# Logic_SchematicV4-NEW.net
KiCad netlist of a schematic drawn in EAGLE
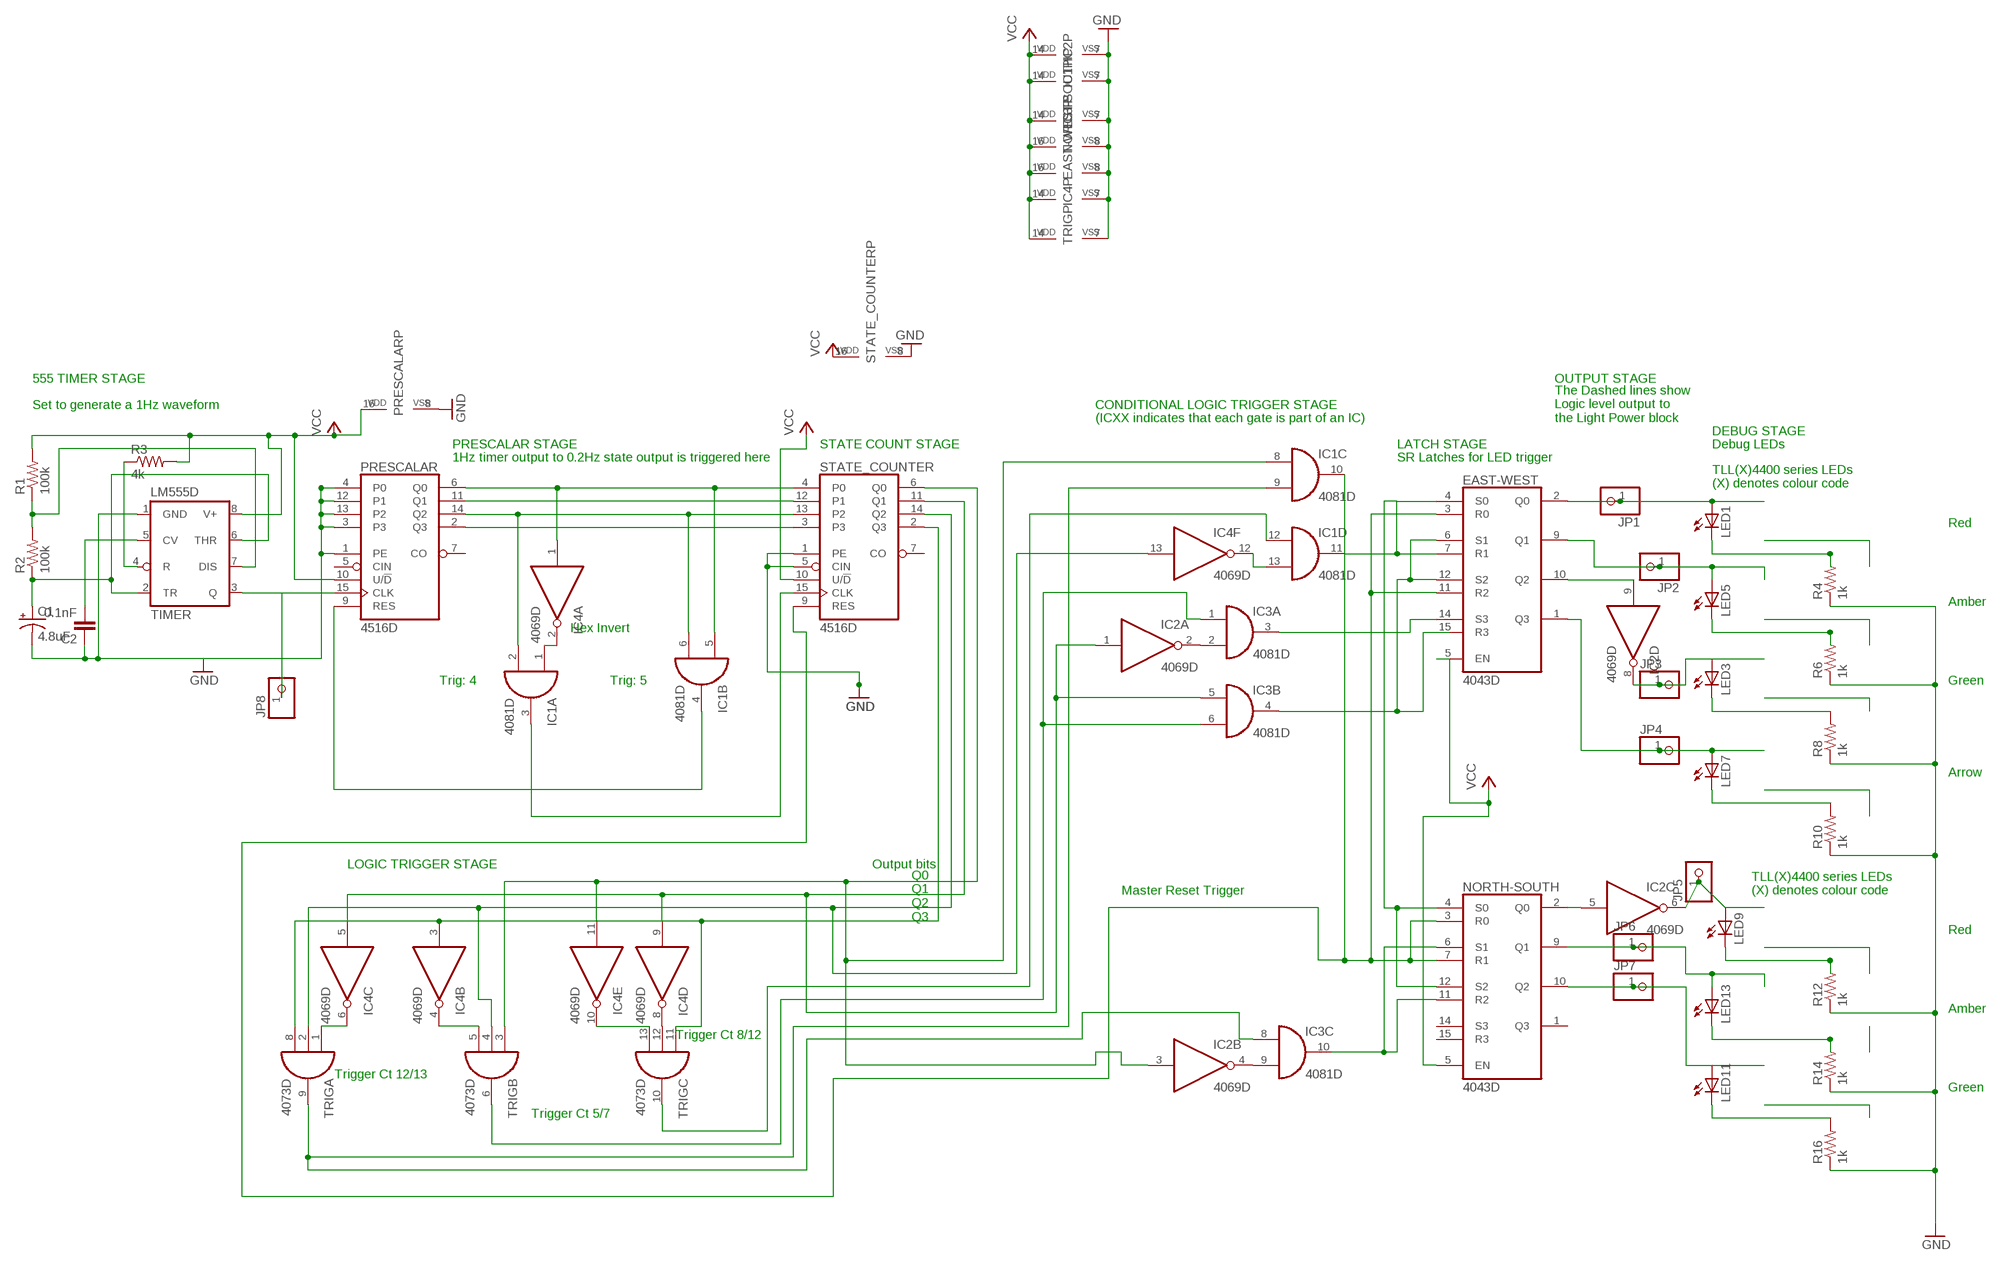
[diagram p0: schematic, sheet 1]

(export (version "E")
  (design (tool "Eeschema 10.0.6"))
  (components
    (comp (ref "C1")
      (value "4.8uF")
      (footprint "eagle-import:E5-8,5")
      (libsource (lib "eagle-import") (part "CPOL-USE5-8.5"))
    )
    (comp (ref "C2")
      (value "0.1nF")
      (footprint "eagle-import:C0805")
      (libsource (lib "eagle-import") (part "C-EUC0805"))
    )
    (comp (ref "EAST-WEST")
      (value "4043D")
      (footprint "eagle-import:SO16")
      (libsource (lib "eagle-import") (part "4043D"))
    )
    (comp (ref "IC1")
      (value "4081D")
      (footprint "eagle-import:SO14")
      (libsource (lib "eagle-import") (part "4081D"))
    )
    (comp (ref "IC2")
      (value "4069D")
      (footprint "eagle-import:SO14")
      (libsource (lib "eagle-import") (part "4069D"))
    )
    (comp (ref "IC3")
      (value "4081D")
      (footprint "eagle-import:SO14")
      (libsource (lib "eagle-import") (part "4081D"))
    )
    (comp (ref "IC4")
      (value "4069D")
      (footprint "eagle-import:SO14")
      (libsource (lib "eagle-import") (part "4069D"))
    )
    (comp (ref "JP1")
      (value "PINHD-1X1")
      (footprint "eagle-import:1X01")
      (libsource (lib "eagle-import") (part "PINHD-1X1"))
    )
    (comp (ref "JP2")
      (value "PINHD-1X1")
      (footprint "eagle-import:1X01")
      (libsource (lib "eagle-import") (part "PINHD-1X1"))
    )
    (comp (ref "JP3")
      (value "PINHD-1X1")
      (footprint "eagle-import:1X01")
      (libsource (lib "eagle-import") (part "PINHD-1X1"))
    )
    (comp (ref "JP4")
      (value "PINHD-1X1")
      (footprint "eagle-import:1X01")
      (libsource (lib "eagle-import") (part "PINHD-1X1"))
    )
    (comp (ref "JP5")
      (value "PINHD-1X1")
      (footprint "eagle-import:1X01")
      (libsource (lib "eagle-import") (part "PINHD-1X1"))
    )
    (comp (ref "JP6")
      (value "PINHD-1X1")
      (footprint "eagle-import:1X01")
      (libsource (lib "eagle-import") (part "PINHD-1X1"))
    )
    (comp (ref "JP7")
      (value "PINHD-1X1")
      (footprint "eagle-import:1X01")
      (libsource (lib "eagle-import") (part "PINHD-1X1"))
    )
    (comp (ref "JP8")
      (value "PINHD-1X1")
      (footprint "eagle-import:1X01")
      (libsource (lib "eagle-import") (part "PINHD-1X1"))
    )
    (comp (ref "LED1")
      (value "LEDCHIP-LED0805")
      (footprint "eagle-import:CHIP-LED0805")
      (libsource (lib "eagle-import") (part "LEDCHIP-LED0805"))
    )
    (comp (ref "LED3")
      (value "LEDCHIP-LED0805")
      (footprint "eagle-import:CHIP-LED0805")
      (libsource (lib "eagle-import") (part "LEDCHIP-LED0805"))
    )
    (comp (ref "LED5")
      (value "LEDCHIP-LED0805")
      (footprint "eagle-import:CHIP-LED0805")
      (libsource (lib "eagle-import") (part "LEDCHIP-LED0805"))
    )
    (comp (ref "LED7")
      (value "LEDCHIP-LED0805")
      (footprint "eagle-import:CHIP-LED0805")
      (libsource (lib "eagle-import") (part "LEDCHIP-LED0805"))
    )
    (comp (ref "LED9")
      (value "LEDCHIP-LED0805")
      (footprint "eagle-import:CHIP-LED0805")
      (libsource (lib "eagle-import") (part "LEDCHIP-LED0805"))
    )
    (comp (ref "LED11")
      (value "LEDCHIP-LED0805")
      (footprint "eagle-import:CHIP-LED0805")
      (libsource (lib "eagle-import") (part "LEDCHIP-LED0805"))
    )
    (comp (ref "LED13")
      (value "LEDCHIP-LED0805")
      (footprint "eagle-import:CHIP-LED0805")
      (libsource (lib "eagle-import") (part "LEDCHIP-LED0805"))
    )
    (comp (ref "NORTH-SOUTH")
      (value "4043D")
      (footprint "eagle-import:SO16")
      (libsource (lib "eagle-import") (part "4043D"))
    )
    (comp (ref "PRESCALAR")
      (value "4516D")
      (footprint "eagle-import:SO16")
      (libsource (lib "eagle-import") (part "4516D"))
    )
    (comp (ref "R1")
      (value "100k")
      (footprint "eagle-import:M0805")
      (libsource (lib "eagle-import") (part "R-US_M0805"))
    )
    (comp (ref "R2")
      (value "100k")
      (footprint "eagle-import:M0805")
      (libsource (lib "eagle-import") (part "R-US_M0805"))
    )
    (comp (ref "R3")
      (value "4k")
      (footprint "eagle-import:M0805")
      (libsource (lib "eagle-import") (part "R-US_M0805"))
    )
    (comp (ref "R4")
      (value "1k")
      (footprint "eagle-import:M0805")
      (libsource (lib "eagle-import") (part "R-US_M0805"))
    )
    (comp (ref "R6")
      (value "1k")
      (footprint "eagle-import:M0805")
      (libsource (lib "eagle-import") (part "R-US_M0805"))
    )
    (comp (ref "R8")
      (value "1k")
      (footprint "eagle-import:M0805")
      (libsource (lib "eagle-import") (part "R-US_M0805"))
    )
    (comp (ref "R10")
      (value "1k")
      (footprint "eagle-import:M0805")
      (libsource (lib "eagle-import") (part "R-US_M0805"))
    )
    (comp (ref "R12")
      (value "1k")
      (footprint "eagle-import:M0805")
      (libsource (lib "eagle-import") (part "R-US_M0805"))
    )
    (comp (ref "R14")
      (value "1k")
      (footprint "eagle-import:M0805")
      (libsource (lib "eagle-import") (part "R-US_M0805"))
    )
    (comp (ref "R16")
      (value "1k")
      (footprint "eagle-import:M0805")
      (libsource (lib "eagle-import") (part "R-US_M0805"))
    )
    (comp (ref "STATE_COUNTER")
      (value "4516D")
      (footprint "eagle-import:SO16")
      (libsource (lib "eagle-import") (part "4516D"))
    )
    (comp (ref "TIMER")
      (value "LM555D")
      (footprint "eagle-import:SO08")
      (libsource (lib "eagle-import") (part "555DLM"))
    )
    (comp (ref "TRIG")
      (value "4073D")
      (footprint "eagle-import:SO14")
      (libsource (lib "eagle-import") (part "4073D"))
    )
  )
  (nets
    (net (code "1") (name "GND") (class "Default")
      (node (ref "C1") (pin "-") (pinfunction "-_-") (pintype "passive"))
      (node (ref "C2") (pin "1") (pinfunction "1_1") (pintype "passive"))
      (node (ref "EAST-WEST") (pin "8") (pinfunction "VSS_8") (pintype "power_in"))
      (node (ref "IC1") (pin "7") (pinfunction "VSS_7") (pintype "power_in"))
      (node (ref "IC2") (pin "7") (pinfunction "VSS_7") (pintype "power_in"))
      (node (ref "IC3") (pin "7") (pinfunction "VSS_7") (pintype "power_in"))
      (node (ref "IC4") (pin "7") (pinfunction "VSS_7") (pintype "power_in"))
      (node (ref "NORTH-SOUTH") (pin "8") (pinfunction "VSS_8") (pintype "power_in"))
      (node (ref "PRESCALAR") (pin "1") (pinfunction "PE_1") (pintype "input"))
      (node (ref "PRESCALAR") (pin "12") (pinfunction "P1_12") (pintype "input"))
      (node (ref "PRESCALAR") (pin "13") (pinfunction "P2_13") (pintype "input"))
      (node (ref "PRESCALAR") (pin "3") (pinfunction "P3_3") (pintype "input"))
      (node (ref "PRESCALAR") (pin "4") (pinfunction "P0_4") (pintype "input"))
      (node (ref "PRESCALAR") (pin "8") (pinfunction "VSS_8") (pintype "power_in"))
      (node (ref "R10") (pin "1") (pinfunction "1_1") (pintype "passive"))
      (node (ref "R12") (pin "1") (pinfunction "1_1") (pintype "passive"))
      (node (ref "R14") (pin "1") (pinfunction "1_1") (pintype "passive"))
      (node (ref "R16") (pin "1") (pinfunction "1_1") (pintype "passive"))
      (node (ref "R4") (pin "1") (pinfunction "1_1") (pintype "passive"))
      (node (ref "R6") (pin "1") (pinfunction "1_1") (pintype "passive"))
      (node (ref "R8") (pin "1") (pinfunction "1_1") (pintype "passive"))
      (node (ref "STATE_COUNTER") (pin "1") (pinfunction "PE_1") (pintype "input"))
      (node (ref "STATE_COUNTER") (pin "5") (pinfunction "CIN_5") (pintype "input"))
      (node (ref "STATE_COUNTER") (pin "8") (pinfunction "VSS_8") (pintype "power_in"))
      (node (ref "TIMER") (pin "1") (pinfunction "GND_1") (pintype "power_in"))
      (node (ref "TRIG") (pin "7") (pinfunction "VSS_7") (pintype "power_in"))
    )
    (net (code "2") (name "Net-(EAST-WESTA-Q0)") (class "Default")
      (node (ref "EAST-WEST") (pin "2") (pinfunction "Q0_2") (pintype "output"))
      (node (ref "JP1") (pin "1") (pinfunction "1_1") (pintype "passive"))
      (node (ref "LED1") (pin "A") (pinfunction "A_A") (pintype "passive"))
    )
    (net (code "3") (name "Net-(EAST-WESTA-Q1)") (class "Default")
      (node (ref "EAST-WEST") (pin "9") (pinfunction "Q1_9") (pintype "output"))
      (node (ref "JP2") (pin "1") (pinfunction "1_1") (pintype "passive"))
      (node (ref "LED5") (pin "A") (pinfunction "A_A") (pintype "passive"))
    )
    (net (code "4") (name "Net-(EAST-WESTA-Q2)") (class "Default")
      (node (ref "EAST-WEST") (pin "10") (pinfunction "Q2_10") (pintype "output"))
      (node (ref "IC2") (pin "9") (pinfunction "I_9") (pintype "input"))
    )
    (net (code "5") (name "Net-(EAST-WESTA-Q3)") (class "Default")
      (node (ref "EAST-WEST") (pin "1") (pinfunction "Q3_1") (pintype "output"))
      (node (ref "JP4") (pin "1") (pinfunction "1_1") (pintype "passive"))
      (node (ref "LED7") (pin "A") (pinfunction "A_A") (pintype "passive"))
    )
    (net (code "6") (name "Net-(EAST-WESTA-R0)") (class "Default")
      (node (ref "EAST-WEST") (pin "11") (pinfunction "R2_11") (pintype "input"))
      (node (ref "EAST-WEST") (pin "3") (pinfunction "R0_3") (pintype "input"))
      (node (ref "IC1") (pin "10") (pinfunction "O_10") (pintype "output"))
      (node (ref "NORTH-SOUTH") (pin "3") (pinfunction "R0_3") (pintype "input"))
      (node (ref "NORTH-SOUTH") (pin "7") (pinfunction "R1_7") (pintype "input"))
      (node (ref "STATE_COUNTER") (pin "9") (pinfunction "RES_9") (pintype "input"))
    )
    (net (code "7") (name "Net-(EAST-WESTA-R1)") (class "Default")
      (node (ref "EAST-WEST") (pin "4") (pinfunction "S0_4") (pintype "input"))
      (node (ref "EAST-WEST") (pin "7") (pinfunction "R1_7") (pintype "input"))
      (node (ref "IC1") (pin "11") (pinfunction "O_11") (pintype "output"))
      (node (ref "NORTH-SOUTH") (pin "12") (pinfunction "S2_12") (pintype "input"))
      (node (ref "NORTH-SOUTH") (pin "4") (pinfunction "S0_4") (pintype "input"))
    )
    (net (code "8") (name "Net-(EAST-WESTA-S1)") (class "Default")
      (node (ref "EAST-WEST") (pin "12") (pinfunction "S2_12") (pintype "input"))
      (node (ref "EAST-WEST") (pin "6") (pinfunction "S1_6") (pintype "input"))
      (node (ref "IC3") (pin "4") (pinfunction "O_4") (pintype "output"))
    )
    (net (code "9") (name "Net-(EAST-WESTA-S3)") (class "Default")
      (node (ref "EAST-WEST") (pin "14") (pinfunction "S3_14") (pintype "input"))
      (node (ref "IC3") (pin "3") (pinfunction "O_3") (pintype "output"))
    )
    (net (code "10") (name "Net-(IC1A-I0)") (class "Default")
      (node (ref "IC1") (pin "1") (pinfunction "I0_1") (pintype "input"))
      (node (ref "IC4") (pin "2") (pinfunction "O_2") (pintype "output"))
    )
    (net (code "11") (name "Net-(IC1A-I1)") (class "Default")
      (node (ref "IC1") (pin "2") (pinfunction "I1_2") (pintype "input"))
      (node (ref "IC1") (pin "6") (pinfunction "I1_6") (pintype "input"))
      (node (ref "PRESCALAR") (pin "14") (pinfunction "Q2_14") (pintype "output"))
      (node (ref "STATE_COUNTER") (pin "13") (pinfunction "P2_13") (pintype "input"))
    )
    (net (code "12") (name "Net-(IC1A-O)") (class "Default")
      (node (ref "IC1") (pin "3") (pinfunction "O_3") (pintype "output"))
      (node (ref "STATE_COUNTER") (pin "15") (pinfunction "CLK_15") (pintype "input"))
    )
    (net (code "13") (name "Net-(IC1B-I0)") (class "Default")
      (node (ref "IC1") (pin "5") (pinfunction "I0_5") (pintype "input"))
      (node (ref "IC4") (pin "1") (pinfunction "I_1") (pintype "input"))
      (node (ref "PRESCALAR") (pin "6") (pinfunction "Q0_6") (pintype "output"))
      (node (ref "STATE_COUNTER") (pin "4") (pinfunction "P0_4") (pintype "input"))
    )
    (net (code "14") (name "Net-(IC1B-O)") (class "Default")
      (node (ref "IC1") (pin "4") (pinfunction "O_4") (pintype "output"))
      (node (ref "PRESCALAR") (pin "9") (pinfunction "RES_9") (pintype "input"))
    )
    (net (code "15") (name "Net-(IC1C-I0)") (class "Default")
      (node (ref "IC1") (pin "8") (pinfunction "I0_8") (pintype "input"))
      (node (ref "IC2") (pin "3") (pinfunction "I_3") (pintype "input"))
      (node (ref "IC4") (pin "11") (pinfunction "I_11") (pintype "input"))
      (node (ref "STATE_COUNTER") (pin "6") (pinfunction "Q0_6") (pintype "output"))
      (node (ref "TRIG") (pin "3") (pinfunction "I0_3") (pintype "input"))
    )
    (net (code "16") (name "Net-(IC1C-I1)") (class "Default")
      (node (ref "IC1") (pin "9") (pinfunction "I1_9") (pintype "input"))
      (node (ref "IC3") (pin "8") (pinfunction "I0_8") (pintype "input"))
      (node (ref "TRIG") (pin "9") (pinfunction "O_9") (pintype "output"))
    )
    (net (code "17") (name "Net-(IC1D-I0)") (class "Default")
      (node (ref "IC1") (pin "12") (pinfunction "I0_12") (pintype "input"))
      (node (ref "TRIG") (pin "10") (pinfunction "O_10") (pintype "output"))
    )
    (net (code "18") (name "Net-(IC1D-I1)") (class "Default")
      (node (ref "IC1") (pin "13") (pinfunction "I1_13") (pintype "input"))
      (node (ref "IC4") (pin "12") (pinfunction "O_12") (pintype "output"))
    )
    (net (code "19") (name "Net-(IC2A-I)") (class "Default")
      (node (ref "IC2") (pin "1") (pinfunction "I_1") (pintype "input"))
      (node (ref "IC3") (pin "5") (pinfunction "I0_5") (pintype "input"))
      (node (ref "IC4") (pin "5") (pinfunction "I_5") (pintype "input"))
      (node (ref "IC4") (pin "9") (pinfunction "I_9") (pintype "input"))
      (node (ref "STATE_COUNTER") (pin "11") (pinfunction "Q1_11") (pintype "output"))
    )
    (net (code "20") (name "Net-(IC2A-O)") (class "Default")
      (node (ref "IC2") (pin "2") (pinfunction "O_2") (pintype "output"))
      (node (ref "IC3") (pin "2") (pinfunction "I1_2") (pintype "input"))
    )
    (net (code "21") (name "Net-(IC2B-O)") (class "Default")
      (node (ref "IC2") (pin "4") (pinfunction "O_4") (pintype "output"))
      (node (ref "IC3") (pin "9") (pinfunction "I1_9") (pintype "input"))
    )
    (net (code "22") (name "Net-(IC2C-I)") (class "Default")
      (node (ref "IC2") (pin "5") (pinfunction "I_5") (pintype "input"))
      (node (ref "NORTH-SOUTH") (pin "2") (pinfunction "Q0_2") (pintype "output"))
    )
    (net (code "23") (name "Net-(IC2C-O)") (class "Default")
      (node (ref "IC2") (pin "6") (pinfunction "O_6") (pintype "output"))
      (node (ref "JP5") (pin "1") (pinfunction "1_1") (pintype "passive"))
      (node (ref "LED9") (pin "A") (pinfunction "A_A") (pintype "passive"))
    )
    (net (code "24") (name "Net-(IC2D-O)") (class "Default")
      (node (ref "IC2") (pin "8") (pinfunction "O_8") (pintype "output"))
      (node (ref "JP3") (pin "1") (pinfunction "1_1") (pintype "passive"))
      (node (ref "LED3") (pin "A") (pinfunction "A_A") (pintype "passive"))
    )
    (net (code "25") (name "Net-(IC3A-I0)") (class "Default")
      (node (ref "IC3") (pin "1") (pinfunction "I0_1") (pintype "input"))
      (node (ref "IC3") (pin "6") (pinfunction "I1_6") (pintype "input"))
      (node (ref "TRIG") (pin "6") (pinfunction "O_6") (pintype "output"))
    )
    (net (code "26") (name "Net-(IC3C-O)") (class "Default")
      (node (ref "IC3") (pin "10") (pinfunction "O_10") (pintype "output"))
      (node (ref "NORTH-SOUTH") (pin "11") (pinfunction "R2_11") (pintype "input"))
      (node (ref "NORTH-SOUTH") (pin "6") (pinfunction "S1_6") (pintype "input"))
    )
    (net (code "27") (name "Net-(IC4B-I)") (class "Default")
      (node (ref "IC4") (pin "3") (pinfunction "I_3") (pintype "input"))
      (node (ref "STATE_COUNTER") (pin "2") (pinfunction "Q3_2") (pintype "output"))
      (node (ref "TRIG") (pin "11") (pinfunction "I0_11") (pintype "input"))
      (node (ref "TRIG") (pin "8") (pinfunction "I2_8") (pintype "input"))
    )
    (net (code "28") (name "Net-(IC4B-O)") (class "Default")
      (node (ref "IC4") (pin "4") (pinfunction "O_4") (pintype "output"))
      (node (ref "TRIG") (pin "5") (pinfunction "I2_5") (pintype "input"))
    )
    (net (code "29") (name "Net-(IC4C-O)") (class "Default")
      (node (ref "IC4") (pin "6") (pinfunction "O_6") (pintype "output"))
      (node (ref "TRIG") (pin "1") (pinfunction "I0_1") (pintype "input"))
    )
    (net (code "30") (name "Net-(IC4D-O)") (class "Default")
      (node (ref "IC4") (pin "8") (pinfunction "O_8") (pintype "output"))
      (node (ref "TRIG") (pin "12") (pinfunction "I1_12") (pintype "input"))
    )
    (net (code "31") (name "Net-(IC4E-O)") (class "Default")
      (node (ref "IC4") (pin "10") (pinfunction "O_10") (pintype "output"))
      (node (ref "TRIG") (pin "13") (pinfunction "I2_13") (pintype "input"))
    )
    (net (code "32") (name "Net-(IC4F-I)") (class "Default")
      (node (ref "IC4") (pin "13") (pinfunction "I_13") (pintype "input"))
      (node (ref "STATE_COUNTER") (pin "14") (pinfunction "Q2_14") (pintype "output"))
      (node (ref "TRIG") (pin "2") (pinfunction "I1_2") (pintype "input"))
      (node (ref "TRIG") (pin "4") (pinfunction "I1_4") (pintype "input"))
    )
    (net (code "33") (name "Net-(LED1-PadC)") (class "Default")
      (node (ref "LED1") (pin "C") (pinfunction "C_C") (pintype "passive"))
      (node (ref "R4") (pin "2") (pinfunction "2_2") (pintype "passive"))
    )
    (net (code "34") (name "Net-(LED3-PadC)") (class "Default")
      (node (ref "LED3") (pin "C") (pinfunction "C_C") (pintype "passive"))
      (node (ref "R8") (pin "2") (pinfunction "2_2") (pintype "passive"))
    )
    (net (code "35") (name "Net-(LED5-PadC)") (class "Default")
      (node (ref "LED5") (pin "C") (pinfunction "C_C") (pintype "passive"))
      (node (ref "R6") (pin "2") (pinfunction "2_2") (pintype "passive"))
    )
    (net (code "36") (name "Net-(LED7-PadC)") (class "Default")
      (node (ref "LED7") (pin "C") (pinfunction "C_C") (pintype "passive"))
      (node (ref "R10") (pin "2") (pinfunction "2_2") (pintype "passive"))
    )
    (net (code "37") (name "Net-(LED9-PadC)") (class "Default")
      (node (ref "LED9") (pin "C") (pinfunction "C_C") (pintype "passive"))
      (node (ref "R12") (pin "2") (pinfunction "2_2") (pintype "passive"))
    )
    (net (code "38") (name "Net-(LED11-PadC)") (class "Default")
      (node (ref "LED11") (pin "C") (pinfunction "C_C") (pintype "passive"))
      (node (ref "R16") (pin "2") (pinfunction "2_2") (pintype "passive"))
    )
    (net (code "39") (name "Net-(LED13-PadC)") (class "Default")
      (node (ref "LED13") (pin "C") (pinfunction "C_C") (pintype "passive"))
      (node (ref "R14") (pin "2") (pinfunction "2_2") (pintype "passive"))
    )
    (net (code "40") (name "Net-(NORTH-SOUTHA-Q1)") (class "Default")
      (node (ref "JP6") (pin "1") (pinfunction "1_1") (pintype "passive"))
      (node (ref "LED13") (pin "A") (pinfunction "A_A") (pintype "passive"))
      (node (ref "NORTH-SOUTH") (pin "9") (pinfunction "Q1_9") (pintype "output"))
    )
    (net (code "41") (name "Net-(NORTH-SOUTHA-Q2)") (class "Default")
      (node (ref "JP7") (pin "1") (pinfunction "1_1") (pintype "passive"))
      (node (ref "LED11") (pin "A") (pinfunction "A_A") (pintype "passive"))
      (node (ref "NORTH-SOUTH") (pin "10") (pinfunction "Q2_10") (pintype "output"))
    )
    (net (code "42") (name "Net-(PRESCALARA-CLK)") (class "Default")
      (node (ref "JP8") (pin "1") (pinfunction "1_1") (pintype "passive"))
      (node (ref "PRESCALAR") (pin "15") (pinfunction "CLK_15") (pintype "input"))
      (node (ref "TIMER") (pin "3") (pinfunction "Q_3") (pintype "output"))
    )
    (net (code "43") (name "Net-(PRESCALARA-Q1)") (class "Default")
      (node (ref "PRESCALAR") (pin "11") (pinfunction "Q1_11") (pintype "output"))
      (node (ref "STATE_COUNTER") (pin "12") (pinfunction "P1_12") (pintype "input"))
    )
    (net (code "44") (name "Net-(PRESCALARA-Q3)") (class "Default")
      (node (ref "PRESCALAR") (pin "2") (pinfunction "Q3_2") (pintype "output"))
      (node (ref "STATE_COUNTER") (pin "3") (pinfunction "P3_3") (pintype "input"))
    )
    (net (code "45") (name "Net-(TIMER-CV)") (class "Default")
      (node (ref "C2") (pin "2") (pinfunction "2_2") (pintype "passive"))
      (node (ref "TIMER") (pin "5") (pinfunction "CV_5") (pintype "input"))
    )
    (net (code "46") (name "Net-(TIMER-DIS)") (class "Default")
      (node (ref "R1") (pin "1") (pinfunction "1_1") (pintype "passive"))
      (node (ref "R2") (pin "2") (pinfunction "2_2") (pintype "passive"))
      (node (ref "TIMER") (pin "7") (pinfunction "DIS_7") (pintype "input"))
    )
    (net (code "47") (name "Net-(TIMER-R)") (class "Default")
      (node (ref "R3") (pin "1") (pinfunction "1_1") (pintype "passive"))
      (node (ref "TIMER") (pin "4") (pinfunction "R_4") (pintype "input"))
    )
    (net (code "48") (name "Net-(TIMER-THR)") (class "Default")
      (node (ref "C1") (pin "+") (pinfunction "+_+") (pintype "passive"))
      (node (ref "R2") (pin "1") (pinfunction "1_1") (pintype "passive"))
      (node (ref "TIMER") (pin "2") (pinfunction "TR_2") (pintype "input"))
      (node (ref "TIMER") (pin "6") (pinfunction "THR_6") (pintype "input"))
    )
    (net (code "49") (name "VCC") (class "Default")
      (node (ref "EAST-WEST") (pin "16") (pinfunction "VDD_16") (pintype "power_in"))
      (node (ref "EAST-WEST") (pin "5") (pinfunction "EN_5") (pintype "input"))
      (node (ref "IC1") (pin "14") (pinfunction "VDD_14") (pintype "power_in"))
      (node (ref "IC2") (pin "14") (pinfunction "VDD_14") (pintype "power_in"))
      (node (ref "IC3") (pin "14") (pinfunction "VDD_14") (pintype "power_in"))
      (node (ref "IC4") (pin "14") (pinfunction "VDD_14") (pintype "power_in"))
      (node (ref "NORTH-SOUTH") (pin "16") (pinfunction "VDD_16") (pintype "power_in"))
      (node (ref "NORTH-SOUTH") (pin "5") (pinfunction "EN_5") (pintype "input"))
      (node (ref "PRESCALAR") (pin "10") (pinfunction "U/~{D}_10") (pintype "input"))
      (node (ref "PRESCALAR") (pin "16") (pinfunction "VDD_16") (pintype "power_in"))
      (node (ref "R1") (pin "2") (pinfunction "2_2") (pintype "passive"))
      (node (ref "R3") (pin "2") (pinfunction "2_2") (pintype "passive"))
      (node (ref "STATE_COUNTER") (pin "10") (pinfunction "U/~{D}_10") (pintype "input"))
      (node (ref "STATE_COUNTER") (pin "16") (pinfunction "VDD_16") (pintype "power_in"))
      (node (ref "TIMER") (pin "8") (pinfunction "V+_8") (pintype "power_in"))
      (node (ref "TRIG") (pin "14") (pinfunction "VDD_14") (pintype "power_in"))
    )
    (net (code "50") (name "unconnected-(EAST-WESTA-R3-Pad15)") (class "Default")
      (node (ref "EAST-WEST") (pin "15") (pinfunction "R3_15") (pintype "input"))
    )
    (net (code "51") (name "unconnected-(NORTH-SOUTHA-Q3-Pad1)") (class "Default")
      (node (ref "NORTH-SOUTH") (pin "1") (pinfunction "Q3_1") (pintype "output"))
    )
    (net (code "52") (name "unconnected-(NORTH-SOUTHA-R3-Pad15)") (class "Default")
      (node (ref "NORTH-SOUTH") (pin "15") (pinfunction "R3_15") (pintype "input"))
    )
    (net (code "53") (name "unconnected-(NORTH-SOUTHA-S3-Pad14)") (class "Default")
      (node (ref "NORTH-SOUTH") (pin "14") (pinfunction "S3_14") (pintype "input"))
    )
    (net (code "54") (name "unconnected-(PRESCALARA-CIN-Pad5)") (class "Default")
      (node (ref "PRESCALAR") (pin "5") (pinfunction "CIN_5") (pintype "input"))
    )
    (net (code "55") (name "unconnected-(PRESCALARA-CO-Pad7)") (class "Default")
      (node (ref "PRESCALAR") (pin "7") (pinfunction "CO_7") (pintype "output"))
    )
    (net (code "56") (name "unconnected-(STATE_COUNTERA-CO-Pad7)") (class "Default")
      (node (ref "STATE_COUNTER") (pin "7") (pinfunction "CO_7") (pintype "output"))
    )
  )
)
